# PRUC-Voltmeter_Config.net
KiCad netlist of a schematic drawn in Altium Designer
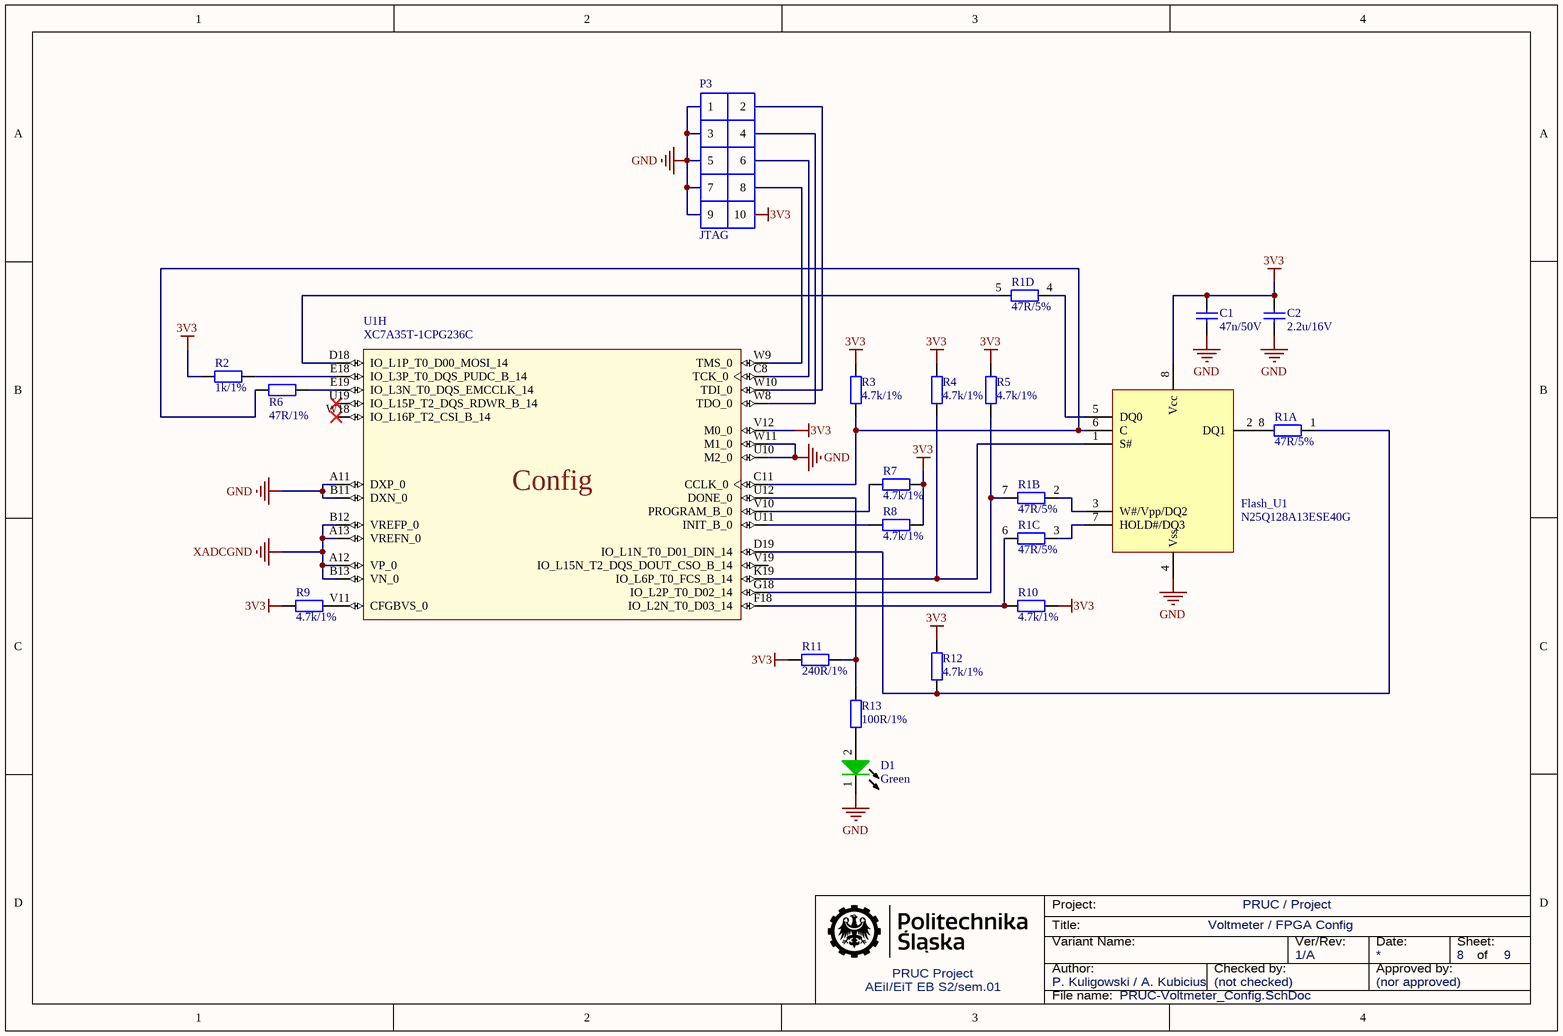
[diagram p0: PRUC-Voltmeter_Config.SchDoc]

(export (version "E")
  (design (tool "Eeschema 10.0.6"))
  (components
    (comp (ref "C1")
      (value "47n/50V")
      (footprint "MLCC_0603")
      (fields (field (name "PART NUMBER") "CL10B473KB8NNNC") (field (name "MANUFACTURER") "Samsung"))
      (libsource (lib "kplabs") (part "Cap"))
    )
    (comp (ref "C2")
      (value "2.2u/16V")
      (footprint "MLCC_0603")
      (fields (field (name "PART NUMBER") "CL10A225KO8NNNC") (field (name "MANUFACTURER") "Samsung"))
      (libsource (lib "kplabs") (part "Cap"))
    )
    (comp (ref "D1")
      (value "Green")
      (footprint "LED_0603_G")
      (fields
        (field (name "PART NUMBER") "KPT-1608MGC")
        (field (name "MANUFACTURER") "Kingbright Electronic")
      )
      (libsource (lib "kplabs") (part "LED_KA_G"))
    )
    (comp (ref "Flash_U1")
      (value "~")
      (footprint "SOIC-8-W")
      (description "128Mbit, 3V Serial NOR Flash Memory")
      (fields
        (field (name "MANUFACTURER") "Micron")
        (field (name "MANUFACTURERPARTNUMBER") "N25Q128A13ESE40G")
      )
      (libsource (lib "microcircuits") (part "N25Q128A13ESE40G"))
    )
    (comp (ref "P3")
      (value "JTAG")
      (footprint "DS1021-10G")
      (fields
        (field (name "PART NUMBER") "ZL202-10G")
        (field (name "MANUFACTURER") "Connfly")
        (field (name "MANUFACTURER PART NUMBER") "DS1021-2*5SF11")
      )
      (libsource (lib "kplabs") (part "Header_2x5_M_Z"))
    )
    (comp (ref "R1")
      (value "47R/5%")
      (footprint "ARRAY_R_0804")
      (fields (field (name "PART NUMBER") "YC124-JR-0747RL") (field (name "MANUFACTURER") "Yageo"))
      (libsource (lib "kplabs") (part "Array_4"))
    )
    (comp (ref "R2")
      (value "1k/1%")
      (footprint "R_0603")
      (fields (field (name "PART NUMBER") "0603SAF1001T5E") (field (name "MANUFACTURER") "Royalohm"))
      (libsource (lib "kplabs") (part "Res"))
    )
    (comp (ref "R3")
      (value "4.7k/1%")
      (footprint "R_0603")
      (fields
        (field (name "PART NUMBER") "0603SAF4701T5E")
        (field (name "MANUFACTURER") "Royalohm")
        (field (name "MANUFACTURER PART NUMBER") "SMD0603-4K7-1%")
      )
      (libsource (lib "") (part "Res_1"))
    )
    (comp (ref "R4")
      (value "4.7k/1%")
      (footprint "R_0603")
      (fields
        (field (name "PART NUMBER") "0603SAF4701T5E")
        (field (name "MANUFACTURER") "Royalohm")
        (field (name "MANUFACTURER PART NUMBER") "SMD0603-4K7-1%")
      )
      (libsource (lib "") (part "Res_1"))
    )
    (comp (ref "R5")
      (value "4.7k/1%")
      (footprint "R_0603")
      (fields
        (field (name "PART NUMBER") "0603SAF4701T5E")
        (field (name "MANUFACTURER") "Royalohm")
        (field (name "MANUFACTURER PART NUMBER") "SMD0603-4K7-1%")
      )
      (libsource (lib "") (part "Res_2"))
    )
    (comp (ref "R6")
      (value "47R/1%")
      (footprint "R_0603")
      (fields (field (name "PART NUMBER") "0603SAF470JT5E") (field (name "MANUFACTURER") "Royalohm"))
      (libsource (lib "kplabs") (part "Res"))
    )
    (comp (ref "R7")
      (value "4.7k/1%")
      (footprint "R_0603")
      (fields
        (field (name "PART NUMBER") "0603SAF4701T5E")
        (field (name "MANUFACTURER") "Royalohm")
        (field (name "MANUFACTURER PART NUMBER") "SMD0603-4K7-1%")
      )
      (libsource (lib "kplabs") (part "Res"))
    )
    (comp (ref "R8")
      (value "4.7k/1%")
      (footprint "R_0603")
      (fields
        (field (name "PART NUMBER") "0603SAF4701T5E")
        (field (name "MANUFACTURER") "Royalohm")
        (field (name "MANUFACTURER PART NUMBER") "SMD0603-4K7-1%")
      )
      (libsource (lib "kplabs") (part "Res"))
    )
    (comp (ref "R9")
      (value "4.7k/1%")
      (footprint "R_0603")
      (fields
        (field (name "PART NUMBER") "0603SAF4701T5E")
        (field (name "MANUFACTURER") "Royalohm")
        (field (name "MANUFACTURER PART NUMBER") "SMD0603-4K7-1%")
      )
      (libsource (lib "kplabs") (part "Res"))
    )
    (comp (ref "R10")
      (value "4.7k/1%")
      (footprint "R_0603")
      (fields
        (field (name "PART NUMBER") "0603SAF4701T5E")
        (field (name "MANUFACTURER") "Royalohm")
        (field (name "MANUFACTURER PART NUMBER") "SMD0603-4K7-1%")
      )
      (libsource (lib "kplabs") (part "Res"))
    )
    (comp (ref "R11")
      (value "240R/1%")
      (footprint "R_0603")
      (fields (field (name "PART NUMBER") "0603SAF0241T5E") (field (name "MANUFACTURER") "Royalohm"))
      (libsource (lib "kplabs") (part "Res"))
    )
    (comp (ref "R12")
      (value "4.7k/1%")
      (footprint "R_0603")
      (fields
        (field (name "PART NUMBER") "0603SAF4701T5E")
        (field (name "MANUFACTURER") "Royalohm")
        (field (name "MANUFACTURER PART NUMBER") "SMD0603-4K7-1%")
      )
      (libsource (lib "") (part "Res_1"))
    )
    (comp (ref "R13")
      (value "100R/1%")
      (footprint "R_1206")
      (fields (field (name "PART NUMBER") "1206S4F1000T5E") (field (name "MANUFACTURER") "Royalohm"))
      (libsource (lib "") (part "Res_1"))
    )
    (comp (ref "U1")
      (value "XC7A35T-1CPG236C")
      (footprint "CPG236-0.5mm")
      (fields (field (name "MANUFACTURER") "Xilinx"))
      (libsource (lib "kplabs") (part "XC7A35T-1CPG236C"))
    )
  )
  (nets
    (net (code "1") (name "3V3") (class "Default")
      (node (ref "C1") (pin "1") (pinfunction "1_1") (pintype "passive"))
      (node (ref "C2") (pin "1") (pinfunction "1_1") (pintype "passive"))
      (node (ref "Flash_U1") (pin "8") (pinfunction "Vcc_8") (pintype "passive"))
      (node (ref "P3") (pin "10") (pinfunction "10_10") (pintype "passive"))
      (node (ref "R10") (pin "2") (pinfunction "2_2") (pintype "passive"))
      (node (ref "R11") (pin "1") (pinfunction "1_1") (pintype "passive"))
      (node (ref "R12") (pin "1") (pinfunction "1_1") (pintype "passive"))
      (node (ref "R2") (pin "1") (pinfunction "1_1") (pintype "passive"))
      (node (ref "R3") (pin "1") (pinfunction "1_1") (pintype "passive"))
      (node (ref "R4") (pin "1") (pinfunction "1_1") (pintype "passive"))
      (node (ref "R5") (pin "2") (pinfunction "2_2") (pintype "passive"))
      (node (ref "R7") (pin "2") (pinfunction "2_2") (pintype "passive"))
      (node (ref "R8") (pin "2") (pinfunction "2_2") (pintype "passive"))
      (node (ref "R9") (pin "1") (pinfunction "1_1") (pintype "passive"))
      (node (ref "U1") (pin "V12") (pinfunction "M0_0_V12") (pintype "bidirectional"))
    )
    (net (code "2") (name "GND") (class "Default")
      (node (ref "C1") (pin "2") (pinfunction "2_2") (pintype "passive"))
      (node (ref "C2") (pin "2") (pinfunction "2_2") (pintype "passive"))
      (node (ref "D1") (pin "1") (pinfunction "K_1") (pintype "passive"))
      (node (ref "Flash_U1") (pin "4") (pinfunction "Vss_4") (pintype "passive"))
      (node (ref "P3") (pin "1") (pinfunction "1_1") (pintype "passive"))
      (node (ref "P3") (pin "3") (pinfunction "3_3") (pintype "passive"))
      (node (ref "P3") (pin "5") (pinfunction "5_5") (pintype "passive"))
      (node (ref "P3") (pin "7") (pinfunction "7_7") (pintype "passive"))
      (node (ref "P3") (pin "9") (pinfunction "9_9") (pintype "passive"))
      (node (ref "U1") (pin "A11") (pinfunction "DXP_0_A11") (pintype "bidirectional"))
      (node (ref "U1") (pin "B11") (pinfunction "DXN_0_B11") (pintype "bidirectional"))
      (node (ref "U1") (pin "U10") (pinfunction "M2_0_U10") (pintype "bidirectional"))
      (node (ref "U1") (pin "W11") (pinfunction "M1_0_W11") (pintype "bidirectional"))
    )
    (net (code "3") (name "Net-(D1-A)") (class "Default")
      (node (ref "D1") (pin "2") (pinfunction "A_2") (pintype "passive"))
      (node (ref "R13") (pin "2") (pinfunction "2_2") (pintype "passive"))
    )
    (net (code "4") (name "Net-(Flash_U1-C)") (class "Default")
      (node (ref "Flash_U1") (pin "6") (pinfunction "C_6") (pintype "passive"))
      (node (ref "R3") (pin "2") (pinfunction "2_2") (pintype "passive"))
      (node (ref "R6") (pin "1") (pinfunction "1_1") (pintype "passive"))
      (node (ref "U1") (pin "C11") (pinfunction "CCLK_0_C11") (pintype "bidirectional"))
    )
    (net (code "5") (name "Net-(Flash_U1-DQ0)") (class "Default")
      (node (ref "Flash_U1") (pin "5") (pinfunction "DQ0_5") (pintype "passive"))
      (node (ref "R1") (pin "4") (pinfunction "4_4") (pintype "passive"))
    )
    (net (code "6") (name "Net-(Flash_U1-DQ1)") (class "Default")
      (node (ref "Flash_U1") (pin "2") (pinfunction "DQ1_2") (pintype "passive"))
      (node (ref "R1") (pin "8") (pinfunction "8_8") (pintype "passive"))
    )
    (net (code "7") (name "Net-(Flash_U1-HOLD#{slash}DQ3)") (class "Default")
      (node (ref "Flash_U1") (pin "7") (pinfunction "HOLD#/DQ3_7") (pintype "passive"))
      (node (ref "R1") (pin "3") (pinfunction "3_3") (pintype "passive"))
    )
    (net (code "8") (name "Net-(Flash_U1-S#)") (class "Default")
      (node (ref "Flash_U1") (pin "1") (pinfunction "S#_1") (pintype "passive"))
      (node (ref "R4") (pin "2") (pinfunction "2_2") (pintype "passive"))
      (node (ref "U1") (pin "K19") (pinfunction "IO_L6P_T0_FCS_B_14_K19") (pintype "bidirectional"))
    )
    (net (code "9") (name "Net-(Flash_U1-W#{slash}Vpp{slash}DQ2)") (class "Default")
      (node (ref "Flash_U1") (pin "3") (pinfunction "W#/Vpp/DQ2_3") (pintype "passive"))
      (node (ref "R1") (pin "2") (pinfunction "2_2") (pintype "passive"))
    )
    (net (code "10") (name "Net-(U1H-CFGBVS_0)") (class "Default")
      (node (ref "R9") (pin "2") (pinfunction "2_2") (pintype "passive"))
      (node (ref "U1") (pin "V11") (pinfunction "CFGBVS_0_V11") (pintype "bidirectional"))
    )
    (net (code "11") (name "Net-(U1H-DONE_0)") (class "Default")
      (node (ref "R11") (pin "2") (pinfunction "2_2") (pintype "passive"))
      (node (ref "R13") (pin "1") (pinfunction "1_1") (pintype "passive"))
      (node (ref "U1") (pin "U12") (pinfunction "DONE_0_U12") (pintype "bidirectional"))
    )
    (net (code "12") (name "Net-(U1H-INIT_B_0)") (class "Default")
      (node (ref "R8") (pin "1") (pinfunction "1_1") (pintype "passive"))
      (node (ref "U1") (pin "U11") (pinfunction "INIT_B_0_U11") (pintype "bidirectional"))
    )
    (net (code "13") (name "Net-(U1H-IO_L1N_T0_D01_DIN_14)") (class "Default")
      (node (ref "R1") (pin "1") (pinfunction "1_1") (pintype "passive"))
      (node (ref "R12") (pin "2") (pinfunction "2_2") (pintype "passive"))
      (node (ref "U1") (pin "D19") (pinfunction "IO_L1N_T0_D01_DIN_14_D19") (pintype "bidirectional"))
    )
    (net (code "14") (name "Net-(U1H-IO_L1P_T0_D00_MOSI_14)") (class "Default")
      (node (ref "R1") (pin "5") (pinfunction "5_5") (pintype "passive"))
      (node (ref "U1") (pin "D18") (pinfunction "IO_L1P_T0_D00_MOSI_14_D18") (pintype "bidirectional"))
    )
    (net (code "15") (name "Net-(U1H-IO_L2N_T0_D03_14)") (class "Default")
      (node (ref "R1") (pin "6") (pinfunction "6_6") (pintype "passive"))
      (node (ref "R10") (pin "1") (pinfunction "1_1") (pintype "passive"))
      (node (ref "U1") (pin "F18") (pinfunction "IO_L2N_T0_D03_14_F18") (pintype "bidirectional"))
    )
    (net (code "16") (name "Net-(U1H-IO_L2P_T0_D02_14)") (class "Default")
      (node (ref "R1") (pin "7") (pinfunction "7_7") (pintype "passive"))
      (node (ref "R5") (pin "1") (pinfunction "1_1") (pintype "passive"))
      (node (ref "U1") (pin "G18") (pinfunction "IO_L2P_T0_D02_14_G18") (pintype "bidirectional"))
    )
    (net (code "17") (name "Net-(U1H-IO_L3N_T0_DQS_EMCCLK_14)") (class "Default")
      (node (ref "R6") (pin "2") (pinfunction "2_2") (pintype "passive"))
      (node (ref "U1") (pin "E19") (pinfunction "IO_L3N_T0_DQS_EMCCLK_14_E19") (pintype "bidirectional"))
    )
    (net (code "18") (name "Net-(U1H-IO_L3P_T0_DQS_PUDC_B_14)") (class "Default")
      (node (ref "R2") (pin "2") (pinfunction "2_2") (pintype "passive"))
      (node (ref "U1") (pin "E18") (pinfunction "IO_L3P_T0_DQS_PUDC_B_14_E18") (pintype "bidirectional"))
    )
    (net (code "19") (name "Net-(U1H-PROGRAM_B_0)") (class "Default")
      (node (ref "R7") (pin "1") (pinfunction "1_1") (pintype "passive"))
      (node (ref "U1") (pin "V10") (pinfunction "PROGRAM_B_0_V10") (pintype "bidirectional"))
    )
    (net (code "20") (name "Net-(U1H-TCK_0)") (class "Default")
      (node (ref "P3") (pin "6") (pinfunction "6_6") (pintype "passive"))
      (node (ref "U1") (pin "C8") (pinfunction "TCK_0_C8") (pintype "bidirectional"))
    )
    (net (code "21") (name "Net-(U1H-TDI_0)") (class "Default")
      (node (ref "P3") (pin "2") (pinfunction "2_2") (pintype "passive"))
      (node (ref "U1") (pin "W10") (pinfunction "TDI_0_W10") (pintype "bidirectional"))
    )
    (net (code "22") (name "Net-(U1H-TDO_0)") (class "Default")
      (node (ref "P3") (pin "4") (pinfunction "4_4") (pintype "passive"))
      (node (ref "U1") (pin "W8") (pinfunction "TDO_0_W8") (pintype "bidirectional"))
    )
    (net (code "23") (name "Net-(U1H-TMS_0)") (class "Default")
      (node (ref "P3") (pin "8") (pinfunction "8_8") (pintype "passive"))
      (node (ref "U1") (pin "W9") (pinfunction "TMS_0_W9") (pintype "bidirectional"))
    )
    (net (code "24") (name "XADCGND") (class "Default")
      (node (ref "U1") (pin "A12") (pinfunction "VP_0_A12") (pintype "bidirectional"))
      (node (ref "U1") (pin "A13") (pinfunction "VREFN_0_A13") (pintype "bidirectional"))
      (node (ref "U1") (pin "B12") (pinfunction "VREFP_0_B12") (pintype "bidirectional"))
      (node (ref "U1") (pin "B13") (pinfunction "VN_0_B13") (pintype "bidirectional"))
    )
    (net (code "25") (name "unconnected-(U1H-IO_L15N_T2_DQS_DOUT_CSO_B_14-PadV19)") (class "Default")
      (node (ref "U1") (pin "V19") (pinfunction "IO_L15N_T2_DQS_DOUT_CSO_B_14_V19") (pintype "bidirectional"))
    )
    (net (code "26") (name "unconnected-(U1H-IO_L15P_T2_DQS_RDWR_B_14-PadU19)") (class "Default")
      (node (ref "U1") (pin "U19") (pinfunction "IO_L15P_T2_DQS_RDWR_B_14_U19") (pintype "bidirectional+no_connect"))
    )
    (net (code "27") (name "unconnected-(U1H-IO_L16P_T2_CSI_B_14-PadW18)") (class "Default")
      (node (ref "U1") (pin "W18") (pinfunction "IO_L16P_T2_CSI_B_14_W18") (pintype "bidirectional+no_connect"))
    )
  )
)
